# Modular-LED-Lamp.net
KiCad netlist of a schematic drawn in EAGLE
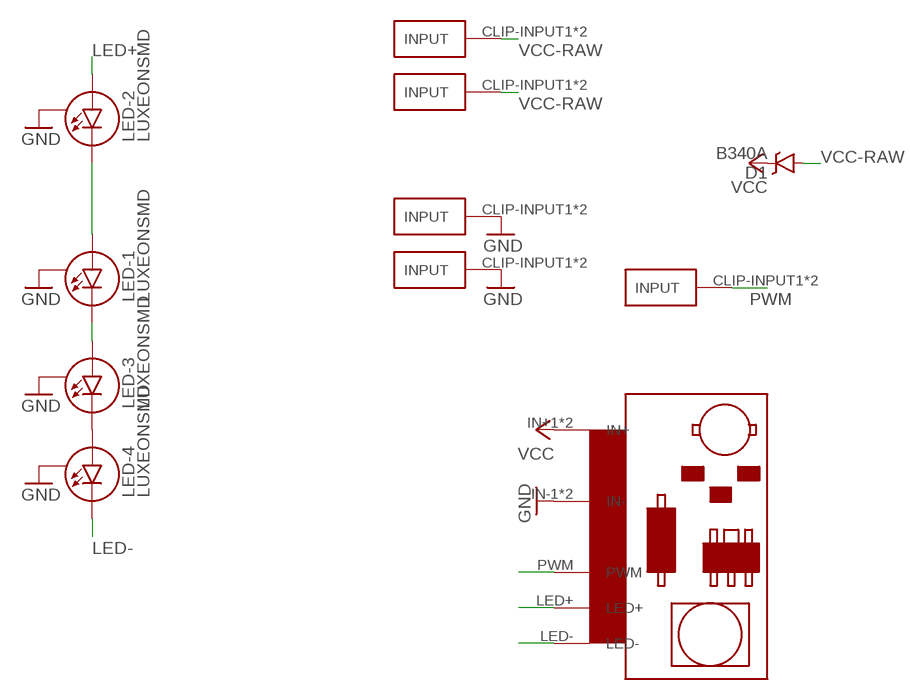
[diagram p0: schematic, sheet 1]

(export (version "E")
  (design (tool "Eeschema 10.0.6"))
  (components
    (comp (ref "D1")
      (value "B340A")
      (footprint "eagle-import:SMA-DIODE")
      (libsource (lib "eagle-import") (part "DIODE-SCHOTTKY-B340A"))
    )
    (comp (ref "GND-CLIP")
      (value "GND")
      (footprint "eagle-import:FUSE-HOLDER-5X20MM")
      (libsource (lib "eagle-import") (part "FUSE-HOLDER-5X20MM"))
    )
    (comp (ref "GND-CLIP2")
      (value "GND")
      (footprint "eagle-import:FUSE-HOLDER-5X20MM")
      (libsource (lib "eagle-import") (part "FUSE-HOLDER-5X20MM"))
    )
    (comp (ref "LED-1")
      (value "LUXEONSMD")
      (footprint "eagle-import:LUXEON")
      (libsource (lib "eagle-import") (part "LUXEONSMD"))
    )
    (comp (ref "LED-2")
      (value "LUXEONSMD")
      (footprint "eagle-import:LUXEON")
      (libsource (lib "eagle-import") (part "LUXEONSMD"))
    )
    (comp (ref "LED-3")
      (value "LUXEONSMD")
      (footprint "eagle-import:LUXEON")
      (libsource (lib "eagle-import") (part "LUXEONSMD"))
    )
    (comp (ref "LED-4")
      (value "LUXEONSMD")
      (footprint "eagle-import:LUXEON")
      (libsource (lib "eagle-import") (part "LUXEONSMD"))
    )
    (comp (ref "PWM-CLIP")
      (value "FUSE-HOLDER-5X20MM")
      (footprint "eagle-import:FUSE-HOLDER-5X20MM")
      (libsource (lib "eagle-import") (part "FUSE-HOLDER-5X20MM"))
    )
    (comp (ref "U$1")
      (value "PT4115-MODULE")
      (footprint "eagle-import:PT4115-MODULE")
      (libsource (lib "eagle-import") (part "PT4115-MODULE"))
    )
    (comp (ref "VCC-CLIP")
      (value "FUSE-HOLDER-5X20MM")
      (footprint "eagle-import:FUSE-HOLDER-5X20MM")
      (libsource (lib "eagle-import") (part "FUSE-HOLDER-5X20MM"))
    )
    (comp (ref "VCC-CLIP2")
      (value "FUSE-HOLDER-5X20MM")
      (footprint "eagle-import:FUSE-HOLDER-5X20MM")
      (libsource (lib "eagle-import") (part "FUSE-HOLDER-5X20MM"))
    )
  )
  (nets
    (net (code "1") (name "/LED+") (class "Default")
      (node (ref "LED-2") (pin "A") (pinfunction "A_A") (pintype "passive"))
      (node (ref "U$1") (pin "LED+") (pinfunction "LED+_LED+") (pintype "bidirectional"))
    )
    (net (code "2") (name "/LED-") (class "Default")
      (node (ref "LED-4") (pin "C") (pinfunction "C_C") (pintype "passive"))
      (node (ref "U$1") (pin "LED-") (pinfunction "LED-_LED-") (pintype "bidirectional"))
    )
    (net (code "3") (name "/PWM") (class "Default")
      (node (ref "PWM-CLIP") (pin "CLIP-INPUT1") (pinfunction "INPUT_CLIP-INPUT1") (pintype "bidirectional"))
      (node (ref "PWM-CLIP") (pin "CLIP-INPUT2") (pinfunction "INPUT_CLIP-INPUT2") (pintype "bidirectional"))
      (node (ref "U$1") (pin "PWM") (pinfunction "PWM_PWM") (pintype "bidirectional"))
    )
    (net (code "4") (name "/VCC-RAW") (class "Default")
      (node (ref "D1") (pin "A") (pinfunction "A_A") (pintype "passive"))
      (node (ref "VCC-CLIP") (pin "CLIP-INPUT1") (pinfunction "INPUT_CLIP-INPUT1") (pintype "bidirectional"))
      (node (ref "VCC-CLIP") (pin "CLIP-INPUT2") (pinfunction "INPUT_CLIP-INPUT2") (pintype "bidirectional"))
      (node (ref "VCC-CLIP2") (pin "CLIP-INPUT1") (pinfunction "INPUT_CLIP-INPUT1") (pintype "bidirectional"))
      (node (ref "VCC-CLIP2") (pin "CLIP-INPUT2") (pinfunction "INPUT_CLIP-INPUT2") (pintype "bidirectional"))
    )
    (net (code "5") (name "GND") (class "Default")
      (node (ref "GND-CLIP") (pin "CLIP-INPUT1") (pinfunction "INPUT_CLIP-INPUT1") (pintype "bidirectional"))
      (node (ref "GND-CLIP") (pin "CLIP-INPUT2") (pinfunction "INPUT_CLIP-INPUT2") (pintype "bidirectional"))
      (node (ref "GND-CLIP2") (pin "CLIP-INPUT1") (pinfunction "INPUT_CLIP-INPUT1") (pintype "bidirectional"))
      (node (ref "GND-CLIP2") (pin "CLIP-INPUT2") (pinfunction "INPUT_CLIP-INPUT2") (pintype "bidirectional"))
      (node (ref "LED-1") (pin "S") (pinfunction "S_S") (pintype "bidirectional"))
      (node (ref "LED-2") (pin "S") (pinfunction "S_S") (pintype "bidirectional"))
      (node (ref "LED-3") (pin "S") (pinfunction "S_S") (pintype "bidirectional"))
      (node (ref "LED-4") (pin "S") (pinfunction "S_S") (pintype "bidirectional"))
      (node (ref "U$1") (pin "IN-1") (pinfunction "IN-_IN-1") (pintype "bidirectional"))
      (node (ref "U$1") (pin "IN-2") (pinfunction "IN-_IN-2") (pintype "bidirectional"))
    )
    (net (code "6") (name "Net-(LED-1-PadA)") (class "Default")
      (node (ref "LED-1") (pin "A") (pinfunction "A_A") (pintype "passive"))
      (node (ref "LED-2") (pin "C") (pinfunction "C_C") (pintype "passive"))
    )
    (net (code "7") (name "Net-(LED-1-PadC)") (class "Default")
      (node (ref "LED-1") (pin "C") (pinfunction "C_C") (pintype "passive"))
      (node (ref "LED-3") (pin "A") (pinfunction "A_A") (pintype "passive"))
    )
    (net (code "8") (name "Net-(LED-3-PadC)") (class "Default")
      (node (ref "LED-3") (pin "C") (pinfunction "C_C") (pintype "passive"))
      (node (ref "LED-4") (pin "A") (pinfunction "A_A") (pintype "passive"))
    )
    (net (code "9") (name "VCC") (class "Default")
      (node (ref "D1") (pin "C") (pinfunction "C_C") (pintype "passive"))
      (node (ref "U$1") (pin "IN+1") (pinfunction "IN+_IN+1") (pintype "bidirectional"))
      (node (ref "U$1") (pin "IN+2") (pinfunction "IN+_IN+2") (pintype "bidirectional"))
    )
  )
)
